# Control.net
KiCad netlist of a schematic drawn in Altium Designer
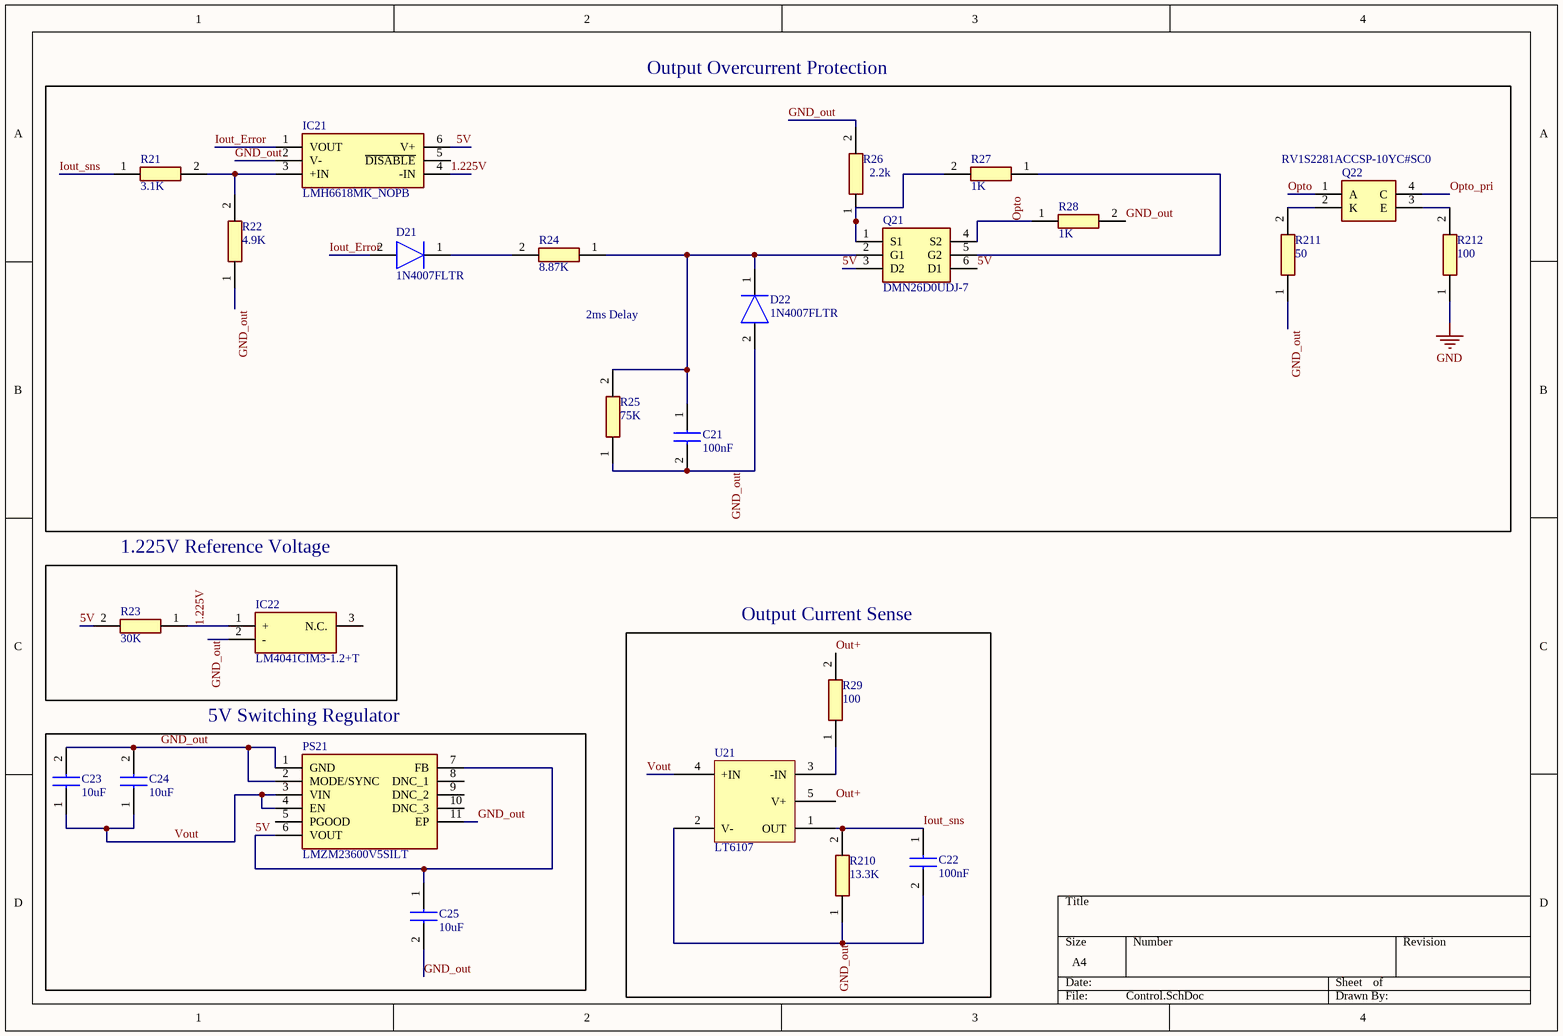
[diagram p0: Control.SchDoc]

(export (version "E")
  (design (tool "Eeschema 10.0.6"))
  (components
    (comp (ref "C21")
      (value "100nF")
      (footprint "SamacSys:CAPC1005X55N")
      (description "Capacitor")
      (fields
        (field (name "MANUFACTURER_PART_NUMBER") "C0402C829D3GACTU")
        (field (name "MOUSER PART NUMBER") "80-C0402C829D3G")
      )
      (libsource (lib "*") (part "C0402C829D3GACTU"))
    )
    (comp (ref "C22")
      (value "100nF")
      (footprint "SamacSys:CAPC1005X55N")
      (description "Capacitor")
      (fields
        (field (name "MANUFACTURER_PART_NUMBER") "C0402C829D3GACTU")
        (field (name "MOUSER PART NUMBER") "80-C0402C829D3G")
      )
      (libsource (lib "*") (part "C0402C829D3GACTU"))
    )
    (comp (ref "C23")
      (value "10uF")
      (footprint "SamacSys:CAPC2012X145N")
      (description "Capacitor")
      (fields
        (field (name "MANUFACTURER_PART_NUMBER") "GCG21BR71H154KA01K")
        (field (name "MOUSER PART NUMBER") "81-GCG21BR71H154KA1K")
      )
      (libsource (lib "*") (part "GCG21BR71H154KA01K"))
    )
    (comp (ref "C24")
      (value "10uF")
      (footprint "SamacSys:CAPC2012X145N")
      (description "Capacitor")
      (fields
        (field (name "MANUFACTURER_PART_NUMBER") "GCG21BR71H154KA01K")
        (field (name "MOUSER PART NUMBER") "81-GCG21BR71H154KA1K")
      )
      (libsource (lib "*") (part "GCG21BR71H154KA01K"))
    )
    (comp (ref "C25")
      (value "10uF")
      (footprint "SamacSys:CAPC2012X145N")
      (description "Capacitor")
      (fields
        (field (name "MANUFACTURER_PART_NUMBER") "GCG21BR71H154KA01K")
        (field (name "MOUSER PART NUMBER") "81-GCG21BR71H154KA1K")
      )
      (libsource (lib "*") (part "GCG21BR71H154KA01K"))
    )
    (comp (ref "D21")
      (value "1N4007FLTR")
      (footprint "SamacSys:SODFL3718X140N")
      (description "Diode")
      (libsource (lib "*") (part "1N4007FLTR"))
    )
    (comp (ref "D22")
      (value "1N4007FLTR")
      (footprint "SamacSys:SODFL3718X140N")
      (description "Diode")
      (libsource (lib "*") (part "1N4007FLTR"))
    )
    (comp (ref "IC21")
      (value "LMH6618MK_NOPB")
      (footprint "SamacSys:SOT95P280X110-6N")
      (description "Integrated Circuit")
      (fields
        (field (name "MANUFACTURER_PART_NUMBER") "LMH6618MK/NOPB")
        (field (name "MOUSER PART NUMBER") "926-LMH6618MK/NOPB")
      )
      (libsource (lib "*") (part "LMH6618MK_NOPB"))
    )
    (comp (ref "IC22")
      (value "LM4041CIM3-1.2+T")
      (footprint "SamacSys:SOT95P237X112-3N")
      (description "Integrated Circuit")
      (fields (field (name "MOUSER PART NUMBER") "700-LM4041CIM3-1.2T"))
      (libsource (lib "*") (part "LM4041CIM3-1.2+T"))
    )
    (comp (ref "PS21")
      (value "LMZM23600V5SILT")
      (footprint "SamacSys:LMZM23600SILT")
      (description "Power Supply")
      (fields (field (name "MOUSER PART NUMBER") "595-LMZM23600V5SILT"))
      (libsource (lib "*") (part "LMZM23600V5SILT"))
    )
    (comp (ref "Q21")
      (value "DMN26D0UDJ-7")
      (footprint "SamacSys:SOTFL35P100X50-6N")
      (description "MOSFET (N-Channel)")
      (fields (field (name "MOUSER PART NUMBER") "621-DMN26D0UDJ-7"))
      (libsource (lib "*") (part "DMN26D0UDJ-7"))
    )
    (comp (ref "Q22")
      (value "RV1S2281ACCSP-10YC#SC0")
      (footprint "SamacSys:SOP130P1020X210-4N")
      (description "Transistor")
      (fields (field (name "MOUSER PART NUMBER") "968-2281ACCSP10YCSC0"))
      (libsource (lib "*") (part "RV1S2281ACCSP-10YC#SC0"))
    )
    (comp (ref "R21")
      (value "3.1K")
      (footprint "SamacSys:ERJ2RKD1004X")
      (description "Resistor")
      (fields (field (name "MANUFACTURER_PART_NUMBER") "ERJ2RKF4023X"))
      (libsource (lib "") (part "ERJ2RKF4023X_2"))
    )
    (comp (ref "R22")
      (value "4.9K")
      (footprint "SamacSys:ERJ2RKD1004X")
      (description "Resistor")
      (fields (field (name "MANUFACTURER_PART_NUMBER") "ERJ2RKF4023X"))
      (libsource (lib "") (part "ERJ2RKF4023X_1"))
    )
    (comp (ref "R23")
      (value "30K")
      (footprint "SamacSys:ERJ2RKD1004X")
      (description "Resistor")
      (fields (field (name "MANUFACTURER_PART_NUMBER") "ERJ2RKF4023X"))
      (libsource (lib "*") (part "ERJ2RKF4023X"))
    )
    (comp (ref "R24")
      (value "8.87K")
      (footprint "SamacSys:ERJ2RKD1004X")
      (description "Resistor")
      (fields (field (name "MANUFACTURER_PART_NUMBER") "ERJ2RKF4023X"))
      (libsource (lib "*") (part "ERJ2RKF4023X"))
    )
    (comp (ref "R25")
      (value "75K")
      (footprint "SamacSys:ERJ2RKD1004X")
      (description "Resistor")
      (fields (field (name "MANUFACTURER_PART_NUMBER") "ERJ2RKF4023X"))
      (libsource (lib "") (part "ERJ2RKF4023X_1"))
    )
    (comp (ref "R26")
      (value "2.2k")
      (footprint "SamacSys:ERJ2RKD1004X")
      (description "Resistor")
      (fields (field (name "MANUFACTURER_PART_NUMBER") "ERJ2RKF4023X"))
      (libsource (lib "") (part "ERJ2RKF4023X_1"))
    )
    (comp (ref "R27")
      (value "1K")
      (footprint "SamacSys:ERJ2RKD1004X")
      (description "Resistor")
      (fields (field (name "MANUFACTURER_PART_NUMBER") "ERJ2RKF4023X"))
      (libsource (lib "*") (part "ERJ2RKF4023X"))
    )
    (comp (ref "R28")
      (value "1K")
      (footprint "SamacSys:ERJ2RKD1004X")
      (description "Resistor")
      (fields (field (name "MANUFACTURER_PART_NUMBER") "ERJ2RKF4023X"))
      (libsource (lib "") (part "ERJ2RKF4023X_2"))
    )
    (comp (ref "R29")
      (value "100")
      (footprint "SamacSys:ERJ2RKD1004X")
      (description "Resistor")
      (fields (field (name "MANUFACTURER_PART_NUMBER") "ERJ2RKF4023X"))
      (libsource (lib "") (part "ERJ2RKF4023X_1"))
    )
    (comp (ref "R210")
      (value "13.3K")
      (footprint "SamacSys:ERJ2RKD1004X")
      (description "Resistor")
      (fields (field (name "MANUFACTURER_PART_NUMBER") "ERJ2RKF4023X"))
      (libsource (lib "") (part "ERJ2RKF4023X_1"))
    )
    (comp (ref "R211")
      (value "50")
      (footprint "SamacSys:ERJ2RKD1004X")
      (description "Resistor")
      (fields (field (name "MANUFACTURER_PART_NUMBER") "ERJ2RKF4023X"))
      (libsource (lib "") (part "ERJ2RKF4023X_1"))
    )
    (comp (ref "R212")
      (value "100")
      (footprint "SamacSys:ERJ2RKD1004X")
      (description "Resistor")
      (fields (field (name "MANUFACTURER_PART_NUMBER") "ERJ2RKF4023X"))
      (libsource (lib "") (part "ERJ2RKF4023X_1"))
    )
    (comp (ref "U21")
      (value "LT6107")
      (footprint "SOT95P245X110-5N")
      (libsource (lib "Schlib1") (part "LT6107"))
    )
  )
  (nets
    (net (code "1") (name "/1.225V") (class "Default")
      (node (ref "IC21") (pin "4") (pinfunction "-IN_4") (pintype "passive"))
      (node (ref "IC22") (pin "1") (pinfunction "+_1") (pintype "passive"))
      (node (ref "R23") (pin "1") (pinfunction "1_1") (pintype "passive"))
    )
    (net (code "2") (name "/5V") (class "Default")
      (node (ref "C25") (pin "1") (pinfunction "1_1") (pintype "passive"))
      (node (ref "IC21") (pin "6") (pinfunction "V+_6") (pintype "passive"))
      (node (ref "PS21") (pin "6") (pinfunction "VOUT_6") (pintype "passive"))
      (node (ref "PS21") (pin "7") (pinfunction "FB_7") (pintype "passive"))
      (node (ref "Q21") (pin "3") (pinfunction "D2_3") (pintype "passive"))
      (node (ref "Q21") (pin "6") (pinfunction "D1_6") (pintype "passive"))
      (node (ref "R23") (pin "2") (pinfunction "2_2") (pintype "passive"))
    )
    (net (code "4") (name "/GND_out") (class "Default")
      (node (ref "C21") (pin "2") (pinfunction "2_2") (pintype "passive"))
      (node (ref "C22") (pin "2") (pinfunction "2_2") (pintype "passive"))
      (node (ref "C23") (pin "2") (pinfunction "2_2") (pintype "passive"))
      (node (ref "C24") (pin "2") (pinfunction "2_2") (pintype "passive"))
      (node (ref "C25") (pin "2") (pinfunction "2_2") (pintype "passive"))
      (node (ref "D22") (pin "2") (pinfunction "A_2") (pintype "passive"))
      (node (ref "IC21") (pin "2") (pinfunction "V-_2") (pintype "passive"))
      (node (ref "IC22") (pin "2") (pinfunction "-_2") (pintype "passive"))
      (node (ref "PS21") (pin "1") (pinfunction "GND_1") (pintype "passive"))
      (node (ref "PS21") (pin "11") (pinfunction "EP_11") (pintype "passive"))
      (node (ref "PS21") (pin "2") (pinfunction "MODE/SYNC_2") (pintype "passive"))
      (node (ref "R210") (pin "1") (pinfunction "1_1") (pintype "passive"))
      (node (ref "R211") (pin "1") (pinfunction "1_1") (pintype "passive"))
      (node (ref "R22") (pin "1") (pinfunction "1_1") (pintype "passive"))
      (node (ref "R25") (pin "1") (pinfunction "1_1") (pintype "passive"))
      (node (ref "R26") (pin "2") (pinfunction "2_2") (pintype "passive"))
      (node (ref "R28") (pin "2") (pinfunction "2_2") (pintype "passive"))
      (node (ref "U21") (pin "2") (pinfunction "V-_2") (pintype "passive"))
    )
    (net (code "5") (name "/Iout_Error") (class "Default")
      (node (ref "D21") (pin "2") (pinfunction "A_2") (pintype "passive"))
      (node (ref "IC21") (pin "1") (pinfunction "VOUT_1") (pintype "passive"))
    )
    (net (code "6") (name "/Iout_sns") (class "Default")
      (node (ref "C22") (pin "1") (pinfunction "1_1") (pintype "passive"))
      (node (ref "R21") (pin "1") (pinfunction "1_1") (pintype "passive"))
      (node (ref "R210") (pin "2") (pinfunction "2_2") (pintype "passive"))
      (node (ref "U21") (pin "1") (pinfunction "OUT_1") (pintype "passive"))
    )
    (net (code "7") (name "/Opto") (class "Default")
      (node (ref "Q21") (pin "4") (pinfunction "S2_4") (pintype "passive"))
      (node (ref "Q22") (pin "1") (pinfunction "A_1") (pintype "passive"))
      (node (ref "R28") (pin "1") (pinfunction "1_1") (pintype "passive"))
    )
    (net (code "8") (name "/Opto_pri") (class "Default")
      (node (ref "Q22") (pin "4") (pinfunction "C_4") (pintype "passive"))
    )
    (net (code "9") (name "/Out+") (class "Default")
      (node (ref "R29") (pin "2") (pinfunction "2_2") (pintype "passive"))
      (node (ref "U21") (pin "5") (pinfunction "V+_5") (pintype "passive"))
    )
    (net (code "10") (name "/Vout") (class "Default")
      (node (ref "C23") (pin "1") (pinfunction "1_1") (pintype "passive"))
      (node (ref "C24") (pin "1") (pinfunction "1_1") (pintype "passive"))
      (node (ref "PS21") (pin "3") (pinfunction "VIN_3") (pintype "passive"))
      (node (ref "PS21") (pin "4") (pinfunction "EN_4") (pintype "passive"))
      (node (ref "U21") (pin "4") (pinfunction "+IN_4") (pintype "passive"))
    )
    (net (code "11") (name "GND") (class "Default")
      (node (ref "R212") (pin "1") (pinfunction "1_1") (pintype "passive"))
    )
    (net (code "12") (name "Net-(D21-K)") (class "Default")
      (node (ref "D21") (pin "1") (pinfunction "K_1") (pintype "passive"))
      (node (ref "R24") (pin "2") (pinfunction "2_2") (pintype "passive"))
    )
    (net (code "13") (name "Net-(D22-K)") (class "Default")
      (node (ref "C21") (pin "1") (pinfunction "1_1") (pintype "passive"))
      (node (ref "D22") (pin "1") (pinfunction "K_1") (pintype "passive"))
      (node (ref "Q21") (pin "2") (pinfunction "G1_2") (pintype "passive"))
      (node (ref "R24") (pin "1") (pinfunction "1_1") (pintype "passive"))
      (node (ref "R25") (pin "2") (pinfunction "2_2") (pintype "passive"))
    )
    (net (code "14") (name "Net-(IC21-+IN)") (class "Default")
      (node (ref "IC21") (pin "3") (pinfunction "+IN_3") (pintype "passive"))
      (node (ref "R21") (pin "2") (pinfunction "2_2") (pintype "passive"))
      (node (ref "R22") (pin "2") (pinfunction "2_2") (pintype "passive"))
    )
    (net (code "15") (name "Net-(Q21-G2)") (class "Default")
      (node (ref "Q21") (pin "5") (pinfunction "G2_5") (pintype "passive"))
      (node (ref "R27") (pin "1") (pinfunction "1_1") (pintype "passive"))
    )
    (net (code "16") (name "Net-(Q21-S1)") (class "Default")
      (node (ref "Q21") (pin "1") (pinfunction "S1_1") (pintype "passive"))
      (node (ref "R26") (pin "1") (pinfunction "1_1") (pintype "passive"))
      (node (ref "R27") (pin "2") (pinfunction "2_2") (pintype "passive"))
    )
    (net (code "17") (name "Net-(Q22-E)") (class "Default")
      (node (ref "Q22") (pin "3") (pinfunction "E_3") (pintype "passive"))
      (node (ref "R212") (pin "2") (pinfunction "2_2") (pintype "passive"))
    )
    (net (code "18") (name "Net-(Q22-K)") (class "Default")
      (node (ref "Q22") (pin "2") (pinfunction "K_2") (pintype "passive"))
      (node (ref "R211") (pin "2") (pinfunction "2_2") (pintype "passive"))
    )
    (net (code "19") (name "Net-(U21--IN)") (class "Default")
      (node (ref "R29") (pin "1") (pinfunction "1_1") (pintype "passive"))
      (node (ref "U21") (pin "3") (pinfunction "-IN_3") (pintype "passive"))
    )
    (net (code "20") (name "unconnected-(IC21-~{DISABLE}-Pad5)") (class "Default")
      (node (ref "IC21") (pin "5") (pinfunction "~{DISABLE}_5") (pintype "passive"))
    )
    (net (code "21") (name "unconnected-(IC22-N.C.-Pad3)") (class "Default")
      (node (ref "IC22") (pin "3") (pinfunction "N.C._3") (pintype "passive"))
    )
    (net (code "22") (name "unconnected-(PS21-DNC_1-Pad8)") (class "Default")
      (node (ref "PS21") (pin "8") (pinfunction "DNC_1_8") (pintype "passive"))
    )
    (net (code "23") (name "unconnected-(PS21-DNC_2-Pad9)") (class "Default")
      (node (ref "PS21") (pin "9") (pinfunction "DNC_2_9") (pintype "passive"))
    )
    (net (code "24") (name "unconnected-(PS21-DNC_3-Pad10)") (class "Default")
      (node (ref "PS21") (pin "10") (pinfunction "DNC_3_10") (pintype "passive"))
    )
    (net (code "25") (name "unconnected-(PS21-PGOOD-Pad5)") (class "Default")
      (node (ref "PS21") (pin "5") (pinfunction "PGOOD_5") (pintype "passive"))
    )
  )
)
